# NAND_gate.net
KiCad netlist of a schematic drawn in EAGLE
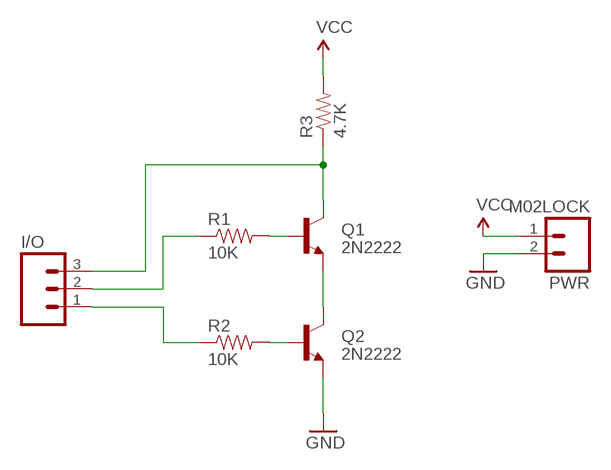
[diagram p0: schematic, sheet 1]

(export (version "E")
  (design (tool "Eeschema 10.0.6"))
  (components
    (comp (ref "I/O")
      (value "M03LOCK")
      (footprint "eagle-import:1X03_LOCK")
      (libsource (lib "eagle-import") (part "M03LOCK"))
    )
    (comp (ref "PWR")
      (value "M02LOCK")
      (footprint "eagle-import:1X02_LOCK")
      (libsource (lib "eagle-import") (part "M02LOCK"))
    )
    (comp (ref "Q1")
      (value "2N2222")
      (footprint "eagle-import:TO-92-AMMO")
      (libsource (lib "eagle-import") (part "TRANSISTOR_NPNTO-92-AMMO"))
    )
    (comp (ref "Q2")
      (value "2N2222")
      (footprint "eagle-import:TO-92-AMMO")
      (libsource (lib "eagle-import") (part "TRANSISTOR_NPNTO-92-AMMO"))
    )
    (comp (ref "R1")
      (value "10K")
      (footprint "eagle-import:AXIAL-0.4")
      (libsource (lib "eagle-import") (part "RESISTORPTH-1/4W"))
    )
    (comp (ref "R2")
      (value "10K")
      (footprint "eagle-import:AXIAL-0.4")
      (libsource (lib "eagle-import") (part "RESISTORPTH-1/4W"))
    )
    (comp (ref "R3")
      (value "4.7K")
      (footprint "eagle-import:AXIAL-0.4")
      (libsource (lib "eagle-import") (part "RESISTORPTH-1/4W"))
    )
  )
  (nets
    (net (code "1") (name "GND") (class "Default")
      (node (ref "PWR") (pin "2") (pinfunction "2_2") (pintype "passive"))
      (node (ref "Q2") (pin "1") (pinfunction "E_1") (pintype "passive"))
    )
    (net (code "2") (name "Net-(Q1-B)") (class "Default")
      (node (ref "Q1") (pin "2") (pinfunction "B_2") (pintype "passive"))
      (node (ref "R1") (pin "P$2") (pinfunction "2_P$2") (pintype "passive"))
    )
    (net (code "3") (name "Net-(Q1-C)") (class "Default")
      (node (ref "I/O") (pin "3") (pinfunction "3_3") (pintype "passive"))
      (node (ref "Q1") (pin "3") (pinfunction "C_3") (pintype "passive"))
      (node (ref "R3") (pin "P$1") (pinfunction "1_P$1") (pintype "passive"))
    )
    (net (code "4") (name "Net-(Q1-E)") (class "Default")
      (node (ref "Q1") (pin "1") (pinfunction "E_1") (pintype "passive"))
      (node (ref "Q2") (pin "3") (pinfunction "C_3") (pintype "passive"))
    )
    (net (code "5") (name "Net-(Q2-B)") (class "Default")
      (node (ref "Q2") (pin "2") (pinfunction "B_2") (pintype "passive"))
      (node (ref "R2") (pin "P$2") (pinfunction "2_P$2") (pintype "passive"))
    )
    (net (code "6") (name "Net-(R1-1)") (class "Default")
      (node (ref "I/O") (pin "2") (pinfunction "2_2") (pintype "passive"))
      (node (ref "R1") (pin "P$1") (pinfunction "1_P$1") (pintype "passive"))
    )
    (net (code "7") (name "Net-(R2-1)") (class "Default")
      (node (ref "I/O") (pin "1") (pinfunction "1_1") (pintype "passive"))
      (node (ref "R2") (pin "P$1") (pinfunction "1_P$1") (pintype "passive"))
    )
    (net (code "8") (name "VCC") (class "Default")
      (node (ref "PWR") (pin "1") (pinfunction "1_1") (pintype "passive"))
      (node (ref "R3") (pin "P$2") (pinfunction "2_P$2") (pintype "passive"))
    )
  )
)
